# SDRAM_hall_crossboard_1_1.net
KiCad netlist of a schematic drawn in Altium Designer
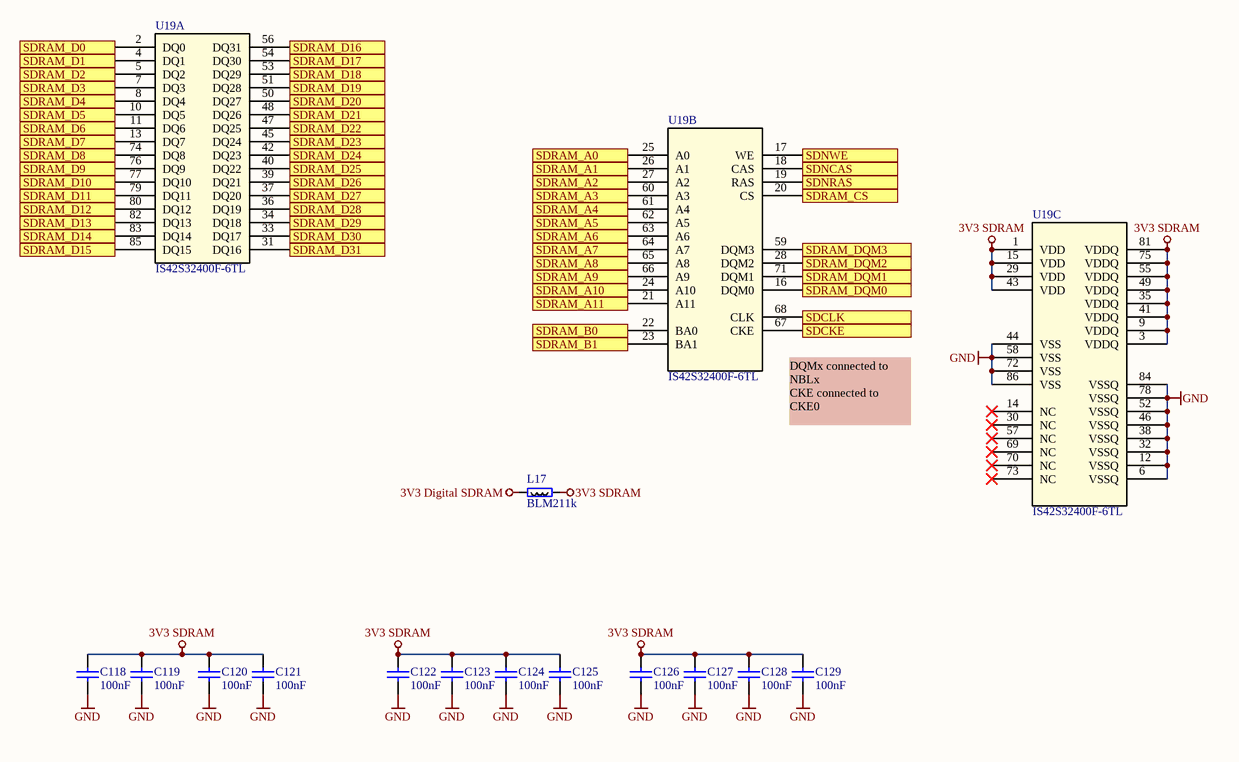
[diagram p0: SDRAM_hall_crossboard_1_1.SchDoc]

(export (version "E")
  (design (tool "Eeschema 10.0.6"))
  (components
    (comp (ref "C118")
      (value "100nF")
      (footprint "hall_crossboard_1_1_library:0603C")
      (description "Capacitor 0402 / 0603 / 0805")
      (libsource (lib "hall_crossboard_1_1_library") (part "Capacitor_ST"))
    )
    (comp (ref "C119")
      (value "100nF")
      (footprint "hall_crossboard_1_1_library:0603C")
      (description "Capacitor 0402 / 0603 / 0805")
      (libsource (lib "hall_crossboard_1_1_library") (part "Capacitor_ST"))
    )
    (comp (ref "C120")
      (value "100nF")
      (footprint "hall_crossboard_1_1_library:0603C")
      (description "Capacitor 0402 / 0603 / 0805")
      (libsource (lib "hall_crossboard_1_1_library") (part "Capacitor_ST"))
    )
    (comp (ref "C121")
      (value "100nF")
      (footprint "hall_crossboard_1_1_library:0603C")
      (description "Capacitor 0402 / 0603 / 0805")
      (libsource (lib "hall_crossboard_1_1_library") (part "Capacitor_ST"))
    )
    (comp (ref "C122")
      (value "100nF")
      (footprint "hall_crossboard_1_1_library:0603C")
      (description "Capacitor 0402 / 0603 / 0805")
      (libsource (lib "hall_crossboard_1_1_library") (part "Capacitor_ST"))
    )
    (comp (ref "C123")
      (value "100nF")
      (footprint "hall_crossboard_1_1_library:0603C")
      (description "Capacitor 0402 / 0603 / 0805")
      (libsource (lib "hall_crossboard_1_1_library") (part "Capacitor_ST"))
    )
    (comp (ref "C124")
      (value "100nF")
      (footprint "hall_crossboard_1_1_library:0603C")
      (description "Capacitor 0402 / 0603 / 0805")
      (libsource (lib "hall_crossboard_1_1_library") (part "Capacitor_ST"))
    )
    (comp (ref "C125")
      (value "100nF")
      (footprint "hall_crossboard_1_1_library:0603C")
      (description "Capacitor 0402 / 0603 / 0805")
      (libsource (lib "hall_crossboard_1_1_library") (part "Capacitor_ST"))
    )
    (comp (ref "C126")
      (value "100nF")
      (footprint "hall_crossboard_1_1_library:0603C")
      (description "Capacitor 0402 / 0603 / 0805")
      (libsource (lib "hall_crossboard_1_1_library") (part "Capacitor_ST"))
    )
    (comp (ref "C127")
      (value "100nF")
      (footprint "hall_crossboard_1_1_library:0603C")
      (description "Capacitor 0402 / 0603 / 0805")
      (libsource (lib "hall_crossboard_1_1_library") (part "Capacitor_ST"))
    )
    (comp (ref "C128")
      (value "100nF")
      (footprint "hall_crossboard_1_1_library:0603C")
      (description "Capacitor 0402 / 0603 / 0805")
      (libsource (lib "hall_crossboard_1_1_library") (part "Capacitor_ST"))
    )
    (comp (ref "C129")
      (value "100nF")
      (footprint "hall_crossboard_1_1_library:0603C")
      (description "Capacitor 0402 / 0603 / 0805")
      (libsource (lib "hall_crossboard_1_1_library") (part "Capacitor_ST"))
    )
    (comp (ref "L17")
      (value "BLM211k")
      (footprint "footprint_hall_crossboard_1_1_library:RESC2012X50N")
      (description "SMD Ferrite bead 0805")
      (libsource (lib "schematic_hall_crossboard_1_1_library") (part "BLM21"))
    )
    (comp (ref "U19")
      (value "IS42S32400F-6TL")
      (footprint "footprint_hall_crossboard_1_1_library:SOP50P1176X120-86N")
      (description "4M x 32\r\n128Mb SYNCHRONOUS DRAM")
      (libsource (lib "schematic_hall_crossboard_1_1_library") (part "IS42S32400F/IS45S32400F"))
    )
  )
  (nets
    (net (code "1") (name "/SDCKE") (class "Default")
      (node (ref "U19") (pin "67") (pinfunction "CKE_67") (pintype "passive"))
    )
    (net (code "2") (name "/SDCLK") (class "Default")
      (node (ref "U19") (pin "68") (pinfunction "CLK_68") (pintype "passive"))
    )
    (net (code "3") (name "/SDNCAS") (class "Default")
      (node (ref "U19") (pin "18") (pinfunction "CAS_18") (pintype "passive"))
    )
    (net (code "4") (name "/SDNRAS") (class "Default")
      (node (ref "U19") (pin "19") (pinfunction "RAS_19") (pintype "passive"))
    )
    (net (code "5") (name "/SDNWE") (class "Default")
      (node (ref "U19") (pin "17") (pinfunction "WE_17") (pintype "passive"))
    )
    (net (code "6") (name "/SDRAM_A0") (class "Default")
      (node (ref "U19") (pin "25") (pinfunction "A0_25") (pintype "passive"))
    )
    (net (code "7") (name "/SDRAM_A1") (class "Default")
      (node (ref "U19") (pin "26") (pinfunction "A1_26") (pintype "passive"))
    )
    (net (code "8") (name "/SDRAM_A2") (class "Default")
      (node (ref "U19") (pin "27") (pinfunction "A2_27") (pintype "passive"))
    )
    (net (code "9") (name "/SDRAM_A3") (class "Default")
      (node (ref "U19") (pin "60") (pinfunction "A3_60") (pintype "passive"))
    )
    (net (code "10") (name "/SDRAM_A4") (class "Default")
      (node (ref "U19") (pin "61") (pinfunction "A4_61") (pintype "passive"))
    )
    (net (code "11") (name "/SDRAM_A5") (class "Default")
      (node (ref "U19") (pin "62") (pinfunction "A5_62") (pintype "passive"))
    )
    (net (code "12") (name "/SDRAM_A6") (class "Default")
      (node (ref "U19") (pin "63") (pinfunction "A6_63") (pintype "passive"))
    )
    (net (code "13") (name "/SDRAM_A7") (class "Default")
      (node (ref "U19") (pin "64") (pinfunction "A7_64") (pintype "passive"))
    )
    (net (code "14") (name "/SDRAM_A8") (class "Default")
      (node (ref "U19") (pin "65") (pinfunction "A8_65") (pintype "passive"))
    )
    (net (code "15") (name "/SDRAM_A9") (class "Default")
      (node (ref "U19") (pin "66") (pinfunction "A9_66") (pintype "passive"))
    )
    (net (code "16") (name "/SDRAM_A10") (class "Default")
      (node (ref "U19") (pin "24") (pinfunction "A10_24") (pintype "passive"))
    )
    (net (code "17") (name "/SDRAM_A11") (class "Default")
      (node (ref "U19") (pin "21") (pinfunction "A11_21") (pintype "passive"))
    )
    (net (code "18") (name "/SDRAM_B0") (class "Default")
      (node (ref "U19") (pin "22") (pinfunction "BA0_22") (pintype "passive"))
    )
    (net (code "19") (name "/SDRAM_B1") (class "Default")
      (node (ref "U19") (pin "23") (pinfunction "BA1_23") (pintype "passive"))
    )
    (net (code "20") (name "/SDRAM_CS") (class "Default")
      (node (ref "U19") (pin "20") (pinfunction "CS_20") (pintype "passive"))
    )
    (net (code "21") (name "/SDRAM_D0") (class "Default")
      (node (ref "U19") (pin "2") (pinfunction "DQ0_2") (pintype "passive"))
    )
    (net (code "22") (name "/SDRAM_D1") (class "Default")
      (node (ref "U19") (pin "4") (pinfunction "DQ1_4") (pintype "passive"))
    )
    (net (code "23") (name "/SDRAM_D2") (class "Default")
      (node (ref "U19") (pin "5") (pinfunction "DQ2_5") (pintype "passive"))
    )
    (net (code "24") (name "/SDRAM_D3") (class "Default")
      (node (ref "U19") (pin "7") (pinfunction "DQ3_7") (pintype "passive"))
    )
    (net (code "25") (name "/SDRAM_D4") (class "Default")
      (node (ref "U19") (pin "8") (pinfunction "DQ4_8") (pintype "passive"))
    )
    (net (code "26") (name "/SDRAM_D5") (class "Default")
      (node (ref "U19") (pin "10") (pinfunction "DQ5_10") (pintype "passive"))
    )
    (net (code "27") (name "/SDRAM_D6") (class "Default")
      (node (ref "U19") (pin "11") (pinfunction "DQ6_11") (pintype "passive"))
    )
    (net (code "28") (name "/SDRAM_D7") (class "Default")
      (node (ref "U19") (pin "13") (pinfunction "DQ7_13") (pintype "passive"))
    )
    (net (code "29") (name "/SDRAM_D8") (class "Default")
      (node (ref "U19") (pin "74") (pinfunction "DQ8_74") (pintype "passive"))
    )
    (net (code "30") (name "/SDRAM_D9") (class "Default")
      (node (ref "U19") (pin "76") (pinfunction "DQ9_76") (pintype "passive"))
    )
    (net (code "31") (name "/SDRAM_D10") (class "Default")
      (node (ref "U19") (pin "77") (pinfunction "DQ10_77") (pintype "passive"))
    )
    (net (code "32") (name "/SDRAM_D11") (class "Default")
      (node (ref "U19") (pin "79") (pinfunction "DQ11_79") (pintype "passive"))
    )
    (net (code "33") (name "/SDRAM_D12") (class "Default")
      (node (ref "U19") (pin "80") (pinfunction "DQ12_80") (pintype "passive"))
    )
    (net (code "34") (name "/SDRAM_D13") (class "Default")
      (node (ref "U19") (pin "82") (pinfunction "DQ13_82") (pintype "passive"))
    )
    (net (code "35") (name "/SDRAM_D14") (class "Default")
      (node (ref "U19") (pin "83") (pinfunction "DQ14_83") (pintype "passive"))
    )
    (net (code "36") (name "/SDRAM_D15") (class "Default")
      (node (ref "U19") (pin "85") (pinfunction "DQ15_85") (pintype "passive"))
    )
    (net (code "37") (name "/SDRAM_D16") (class "Default")
      (node (ref "U19") (pin "56") (pinfunction "DQ31_56") (pintype "passive"))
    )
    (net (code "38") (name "/SDRAM_D17") (class "Default")
      (node (ref "U19") (pin "54") (pinfunction "DQ30_54") (pintype "passive"))
    )
    (net (code "39") (name "/SDRAM_D18") (class "Default")
      (node (ref "U19") (pin "53") (pinfunction "DQ29_53") (pintype "passive"))
    )
    (net (code "40") (name "/SDRAM_D19") (class "Default")
      (node (ref "U19") (pin "51") (pinfunction "DQ28_51") (pintype "passive"))
    )
    (net (code "41") (name "/SDRAM_D20") (class "Default")
      (node (ref "U19") (pin "50") (pinfunction "DQ27_50") (pintype "passive"))
    )
    (net (code "42") (name "/SDRAM_D21") (class "Default")
      (node (ref "U19") (pin "48") (pinfunction "DQ26_48") (pintype "passive"))
    )
    (net (code "43") (name "/SDRAM_D22") (class "Default")
      (node (ref "U19") (pin "47") (pinfunction "DQ25_47") (pintype "passive"))
    )
    (net (code "44") (name "/SDRAM_D23") (class "Default")
      (node (ref "U19") (pin "45") (pinfunction "DQ24_45") (pintype "passive"))
    )
    (net (code "45") (name "/SDRAM_D24") (class "Default")
      (node (ref "U19") (pin "42") (pinfunction "DQ23_42") (pintype "passive"))
    )
    (net (code "46") (name "/SDRAM_D25") (class "Default")
      (node (ref "U19") (pin "40") (pinfunction "DQ22_40") (pintype "passive"))
    )
    (net (code "47") (name "/SDRAM_D26") (class "Default")
      (node (ref "U19") (pin "39") (pinfunction "DQ21_39") (pintype "passive"))
    )
    (net (code "48") (name "/SDRAM_D27") (class "Default")
      (node (ref "U19") (pin "37") (pinfunction "DQ20_37") (pintype "passive"))
    )
    (net (code "49") (name "/SDRAM_D28") (class "Default")
      (node (ref "U19") (pin "36") (pinfunction "DQ19_36") (pintype "passive"))
    )
    (net (code "50") (name "/SDRAM_D29") (class "Default")
      (node (ref "U19") (pin "34") (pinfunction "DQ18_34") (pintype "passive"))
    )
    (net (code "51") (name "/SDRAM_D30") (class "Default")
      (node (ref "U19") (pin "33") (pinfunction "DQ17_33") (pintype "passive"))
    )
    (net (code "52") (name "/SDRAM_D31") (class "Default")
      (node (ref "U19") (pin "31") (pinfunction "DQ16_31") (pintype "passive"))
    )
    (net (code "53") (name "/SDRAM_DQM0") (class "Default")
      (node (ref "U19") (pin "16") (pinfunction "DQM0_16") (pintype "passive"))
    )
    (net (code "54") (name "/SDRAM_DQM1") (class "Default")
      (node (ref "U19") (pin "71") (pinfunction "DQM1_71") (pintype "passive"))
    )
    (net (code "55") (name "/SDRAM_DQM2") (class "Default")
      (node (ref "U19") (pin "28") (pinfunction "DQM2_28") (pintype "passive"))
    )
    (net (code "56") (name "/SDRAM_DQM3") (class "Default")
      (node (ref "U19") (pin "59") (pinfunction "DQM3_59") (pintype "passive"))
    )
    (net (code "57") (name "3V3 Digital SDRAM") (class "Default")
      (node (ref "L17") (pin "1") (pinfunction "1_1") (pintype "passive"))
    )
    (net (code "58") (name "3V3 SDRAM") (class "Default")
      (node (ref "C118") (pin "2") (pinfunction "2_2") (pintype "passive"))
      (node (ref "C119") (pin "2") (pinfunction "2_2") (pintype "passive"))
      (node (ref "C120") (pin "2") (pinfunction "2_2") (pintype "passive"))
      (node (ref "C121") (pin "2") (pinfunction "2_2") (pintype "passive"))
      (node (ref "C122") (pin "2") (pinfunction "2_2") (pintype "passive"))
      (node (ref "C123") (pin "2") (pinfunction "2_2") (pintype "passive"))
      (node (ref "C124") (pin "2") (pinfunction "2_2") (pintype "passive"))
      (node (ref "C125") (pin "2") (pinfunction "2_2") (pintype "passive"))
      (node (ref "C126") (pin "2") (pinfunction "2_2") (pintype "passive"))
      (node (ref "C127") (pin "2") (pinfunction "2_2") (pintype "passive"))
      (node (ref "C128") (pin "2") (pinfunction "2_2") (pintype "passive"))
      (node (ref "C129") (pin "1") (pinfunction "1_1") (pintype "passive"))
      (node (ref "L17") (pin "2") (pinfunction "2_2") (pintype "passive"))
      (node (ref "U19") (pin "1") (pinfunction "VDD_1") (pintype "power_in"))
      (node (ref "U19") (pin "15") (pinfunction "VDD_15") (pintype "power_in"))
      (node (ref "U19") (pin "29") (pinfunction "VDD_29") (pintype "power_in"))
      (node (ref "U19") (pin "3") (pinfunction "VDDQ_3") (pintype "power_in"))
      (node (ref "U19") (pin "35") (pinfunction "VDDQ_35") (pintype "power_in"))
      (node (ref "U19") (pin "41") (pinfunction "VDDQ_41") (pintype "power_in"))
      (node (ref "U19") (pin "43") (pinfunction "VDD_43") (pintype "power_in"))
      (node (ref "U19") (pin "49") (pinfunction "VDDQ_49") (pintype "power_in"))
      (node (ref "U19") (pin "55") (pinfunction "VDDQ_55") (pintype "power_in"))
      (node (ref "U19") (pin "75") (pinfunction "VDDQ_75") (pintype "power_in"))
      (node (ref "U19") (pin "81") (pinfunction "VDDQ_81") (pintype "power_in"))
      (node (ref "U19") (pin "9") (pinfunction "VDDQ_9") (pintype "power_in"))
    )
    (net (code "59") (name "GND") (class "Default")
      (node (ref "C118") (pin "1") (pinfunction "1_1") (pintype "passive"))
      (node (ref "C119") (pin "1") (pinfunction "1_1") (pintype "passive"))
      (node (ref "C120") (pin "1") (pinfunction "1_1") (pintype "passive"))
      (node (ref "C121") (pin "1") (pinfunction "1_1") (pintype "passive"))
      (node (ref "C122") (pin "1") (pinfunction "1_1") (pintype "passive"))
      (node (ref "C123") (pin "1") (pinfunction "1_1") (pintype "passive"))
      (node (ref "C124") (pin "1") (pinfunction "1_1") (pintype "passive"))
      (node (ref "C125") (pin "1") (pinfunction "1_1") (pintype "passive"))
      (node (ref "C126") (pin "1") (pinfunction "1_1") (pintype "passive"))
      (node (ref "C127") (pin "1") (pinfunction "1_1") (pintype "passive"))
      (node (ref "C128") (pin "1") (pinfunction "1_1") (pintype "passive"))
      (node (ref "C129") (pin "2") (pinfunction "2_2") (pintype "passive"))
      (node (ref "U19") (pin "12") (pinfunction "VSSQ_12") (pintype "power_in"))
      (node (ref "U19") (pin "32") (pinfunction "VSSQ_32") (pintype "power_in"))
      (node (ref "U19") (pin "38") (pinfunction "VSSQ_38") (pintype "power_in"))
      (node (ref "U19") (pin "44") (pinfunction "VSS_44") (pintype "power_in"))
      (node (ref "U19") (pin "46") (pinfunction "VSSQ_46") (pintype "power_in"))
      (node (ref "U19") (pin "52") (pinfunction "VSSQ_52") (pintype "power_in"))
      (node (ref "U19") (pin "58") (pinfunction "VSS_58") (pintype "power_in"))
      (node (ref "U19") (pin "6") (pinfunction "VSSQ_6") (pintype "power_in"))
      (node (ref "U19") (pin "72") (pinfunction "VSS_72") (pintype "power_in"))
      (node (ref "U19") (pin "78") (pinfunction "VSSQ_78") (pintype "power_in"))
      (node (ref "U19") (pin "84") (pinfunction "VSSQ_84") (pintype "power_in"))
      (node (ref "U19") (pin "86") (pinfunction "VSS_86") (pintype "power_in"))
    )
    (net (code "60") (name "unconnected-(U19C-NC-Pad14)") (class "Default")
      (node (ref "U19") (pin "14") (pinfunction "NC_14") (pintype "power_in+no_connect"))
    )
    (net (code "61") (name "unconnected-(U19C-NC-Pad30)") (class "Default")
      (node (ref "U19") (pin "30") (pinfunction "NC_30") (pintype "power_in+no_connect"))
    )
    (net (code "62") (name "unconnected-(U19C-NC-Pad57)") (class "Default")
      (node (ref "U19") (pin "57") (pinfunction "NC_57") (pintype "power_in+no_connect"))
    )
    (net (code "63") (name "unconnected-(U19C-NC-Pad69)") (class "Default")
      (node (ref "U19") (pin "69") (pinfunction "NC_69") (pintype "power_in+no_connect"))
    )
    (net (code "64") (name "unconnected-(U19C-NC-Pad70)") (class "Default")
      (node (ref "U19") (pin "70") (pinfunction "NC_70") (pintype "power_in+no_connect"))
    )
    (net (code "65") (name "unconnected-(U19C-NC-Pad73)") (class "Default")
      (node (ref "U19") (pin "73") (pinfunction "NC_73") (pintype "power_in+no_connect"))
    )
  )
)
